# TemporizadorArmando.net
KiCad netlist of a schematic drawn in Altium Designer
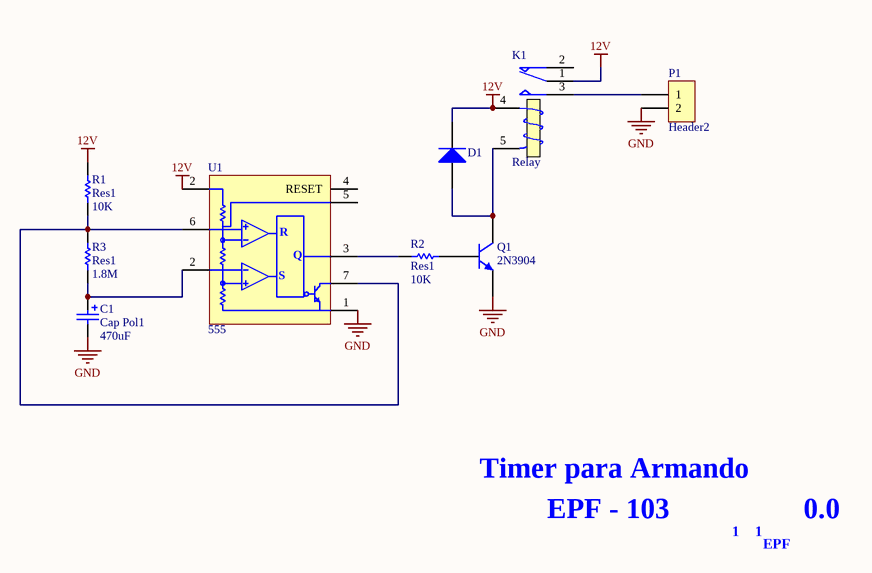
[diagram p0: TemporizadorArmando.SchDoc]

(export (version "E")
  (design (tool "Eeschema 10.0.6"))
  (components
    (comp (ref "C1")
      (value "Cap Pol1")
      (footprint "RB7.6-15")
      (description "Polarized Capacitor (Radial)")
      (fields (field (name "ALTIUM_VALUE") "470uF") (field (name "PUBLISHER") "Altium Limited"))
      (libsource (lib "epf") (part "Cap Pol1"))
    )
    (comp (ref "D1")
      (value "Diode 1N4001")
      (footprint "DO-41")
      (description "1 Amp General Purpose Rectifier")
      (fields (field (name "PUBLISHER") "Altium Limited"))
      (libsource (lib "Miscellaneous Devices") (part "Diode 1N4001"))
    )
    (comp (ref "K1")
      (value "Relay")
      (footprint "MODULE5B")
      (description "SPDT Relay")
      (fields (field (name "PUBLISHER") "Altium Limited"))
      (libsource (lib "Miscellaneous Devices") (part "Relay"))
    )
    (comp (ref "P1") (value "Header2") (footprint "Header2Macho") (libsource (lib "epf") (part "Header2")))
    (comp (ref "Q1")
      (value "2N3904")
      (footprint "BCY-W3/E4")
      (description "NPN General Purpose Amplifier")
      (fields (field (name "PUBLISHER") "Altium Limited"))
      (libsource (lib "epf") (part "2N3904"))
    )
    (comp (ref "R1")
      (value "Res1")
      (footprint "AXIAL-0.3 3D")
      (description "Resistor")
      (fields (field (name "ALTIUM_VALUE") "10K") (field (name "PUBLISHER") "Altium Limited"))
      (libsource (lib "epf") (part "Res1"))
    )
    (comp (ref "R2")
      (value "Res1")
      (footprint "AXIAL-0.3 3D")
      (description "Resistor")
      (fields (field (name "ALTIUM_VALUE") "10K") (field (name "PUBLISHER") "Altium Limited"))
      (libsource (lib "epf") (part "Res1"))
    )
    (comp (ref "R3")
      (value "Res1")
      (footprint "AXIAL-0.3 3D")
      (description "Resistor")
      (fields (field (name "ALTIUM_VALUE") "1.8M") (field (name "PUBLISHER") "Altium Limited"))
      (libsource (lib "epf") (part "Res1"))
    )
    (comp (ref "U1") (value "555") (libsource (lib "epf") (part "NE555")))
  )
  (nets
    (net (code "1") (name "12V") (class "Default")
      (node (ref "D1") (pin "2") (pinfunction "K_2") (pintype "passive"))
      (node (ref "K1") (pin "1") (pinfunction "COM_1") (pintype "passive"))
      (node (ref "K1") (pin "4") (pinfunction "T1_4") (pintype "passive"))
      (node (ref "R1") (pin "2") (pinfunction "2_2") (pintype "passive"))
      (node (ref "U1") (pin "2") (pinfunction "8_2") (pintype "passive"))
    )
    (net (code "2") (name "GND") (class "Default")
      (node (ref "C1") (pin "2") (pinfunction "2_2") (pintype "passive"))
      (node (ref "P1") (pin "2") (pinfunction "2_2") (pintype "passive"))
      (node (ref "Q1") (pin "1") (pinfunction "E_1") (pintype "passive"))
      (node (ref "U1") (pin "1") (pinfunction "GND_1") (pintype "passive"))
    )
    (net (code "3") (name "Net-(D1-A)") (class "Default")
      (node (ref "D1") (pin "1") (pinfunction "A_1") (pintype "passive"))
      (node (ref "K1") (pin "5") (pinfunction "T2_5") (pintype "passive"))
      (node (ref "Q1") (pin "3") (pinfunction "C_3") (pintype "passive"))
    )
    (net (code "4") (name "Net-(K1-NO)") (class "Default")
      (node (ref "K1") (pin "3") (pinfunction "NO_3") (pintype "passive"))
      (node (ref "P1") (pin "1") (pinfunction "1_1") (pintype "passive"))
    )
    (net (code "5") (name "Net-(Q1-B)") (class "Default")
      (node (ref "Q1") (pin "2") (pinfunction "B_2") (pintype "passive"))
      (node (ref "R2") (pin "2") (pinfunction "2_2") (pintype "passive"))
    )
    (net (code "6") (name "Net-(U1-DISCHARGE)") (class "Default")
      (node (ref "R1") (pin "1") (pinfunction "1_1") (pintype "passive"))
      (node (ref "R3") (pin "2") (pinfunction "2_2") (pintype "passive"))
      (node (ref "U1") (pin "6") (pinfunction "THRESHOLD_6") (pintype "passive"))
      (node (ref "U1") (pin "7") (pinfunction "DISCHARGE_7") (pintype "passive"))
    )
    (net (code "7") (name "Net-(U1-OUT)") (class "Default")
      (node (ref "R2") (pin "1") (pinfunction "1_1") (pintype "passive"))
      (node (ref "U1") (pin "3") (pinfunction "OUT_3") (pintype "passive"))
    )
    (net (code "8") (name "Net-(U1-TRIGGER)") (class "Default")
      (node (ref "C1") (pin "1") (pinfunction "1_1") (pintype "passive"))
      (node (ref "R3") (pin "1") (pinfunction "1_1") (pintype "passive"))
      (node (ref "U1") (pin "2") (pinfunction "TRIGGER_2") (pintype "passive"))
    )
    (net (code "9") (name "unconnected-(K1-NC-Pad2)") (class "Default")
      (node (ref "K1") (pin "2") (pinfunction "NC_2") (pintype "passive"))
    )
    (net (code "10") (name "unconnected-(U1-CONTROL_VOLTAGE-Pad5)") (class "Default")
      (node (ref "U1") (pin "5") (pinfunction "CONTROL_VOLTAGE_5") (pintype "passive"))
    )
    (net (code "11") (name "unconnected-(U1-RESET-Pad4)") (class "Default")
      (node (ref "U1") (pin "4") (pinfunction "RESET_4") (pintype "passive"))
    )
  )
)
